# generator.net
KiCad netlist of a schematic drawn in EAGLE
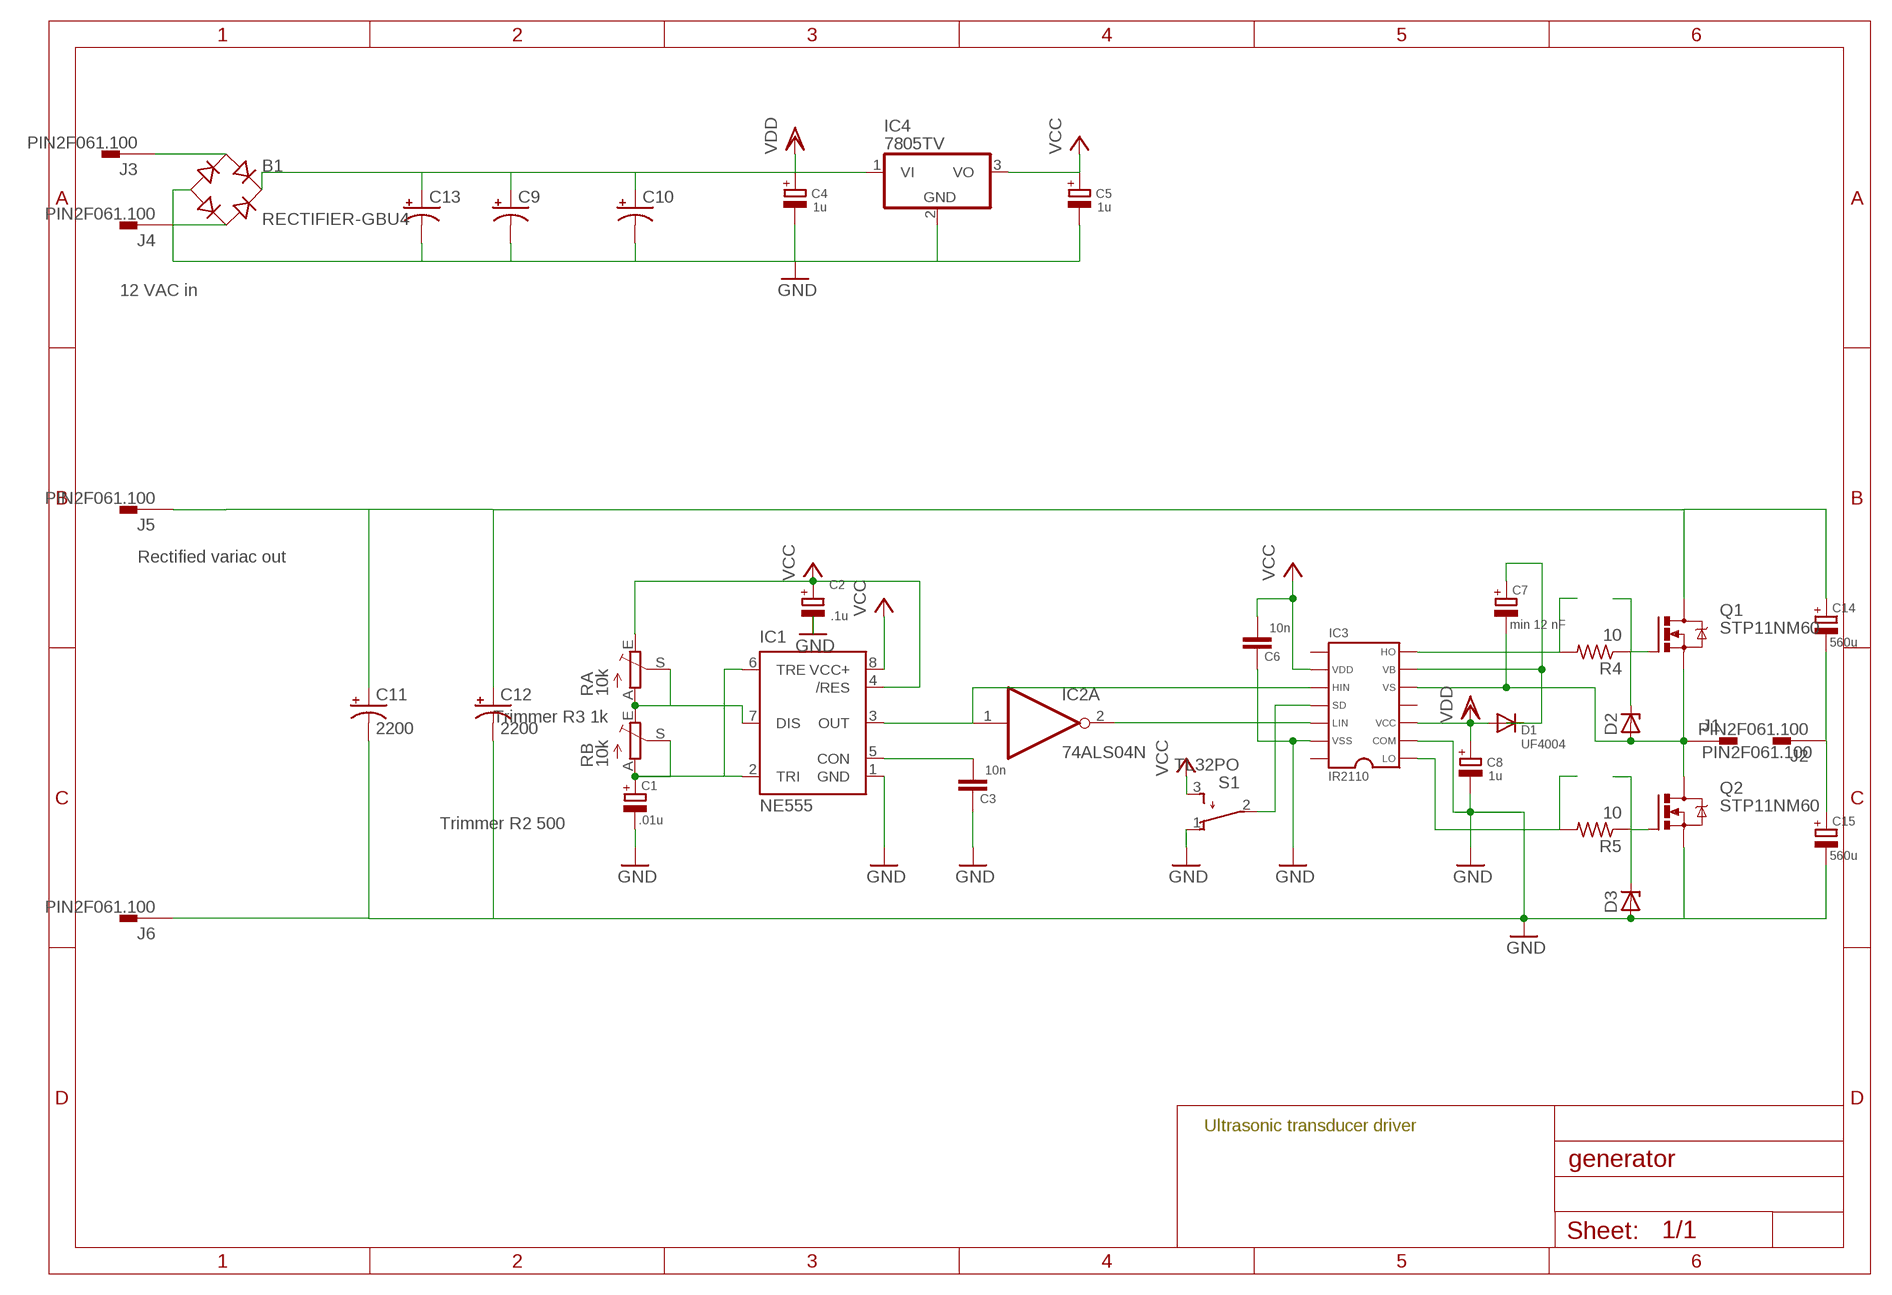
[diagram p0: schematic, sheet 1]

(export (version "E")
  (design (tool "Eeschema 10.0.6"))
  (components
    (comp (ref "B1")
      (value "RECTIFIER-GBU4")
      (footprint "eagle-import:GBU4")
      (libsource (lib "eagle-import") (part "RECTIFIER-GBU4"))
    )
    (comp (ref "C1")
      (value ".01u")
      (footprint "eagle-import:E5-8,5")
      (libsource (lib "eagle-import") (part "CPOL-EUE5-8.5"))
    )
    (comp (ref "C2")
      (value ".1u")
      (footprint "eagle-import:E5-8,5")
      (libsource (lib "eagle-import") (part "CPOL-EUE5-8.5"))
    )
    (comp (ref "C3")
      (value "10n")
      (footprint "eagle-import:C075-052X106")
      (libsource (lib "eagle-import") (part "C-EU075-052X106"))
    )
    (comp (ref "C4")
      (value "1u")
      (footprint "eagle-import:E5-8,5")
      (libsource (lib "eagle-import") (part "CPOL-EUE5-8.5"))
    )
    (comp (ref "C5")
      (value "1u")
      (footprint "eagle-import:E5-8,5")
      (libsource (lib "eagle-import") (part "CPOL-EUE5-8.5"))
    )
    (comp (ref "C6")
      (value "10n")
      (footprint "eagle-import:C075-052X106")
      (libsource (lib "eagle-import") (part "C-EU075-052X106"))
    )
    (comp (ref "C7")
      (value "min 12 nF")
      (footprint "eagle-import:E5-8,5")
      (libsource (lib "eagle-import") (part "CPOL-EUE5-8.5"))
    )
    (comp (ref "C8")
      (value "1u")
      (footprint "eagle-import:E5-8,5")
      (libsource (lib "eagle-import") (part "CPOL-EUE5-8.5"))
    )
    (comp (ref "C9")
      (value "CPOL-USE7.5-18")
      (footprint "eagle-import:E7,5-18")
      (libsource (lib "eagle-import") (part "CPOL-USE7.5-18"))
    )
    (comp (ref "C10")
      (value "CPOL-USE7.5-18")
      (footprint "eagle-import:E7,5-18")
      (libsource (lib "eagle-import") (part "CPOL-USE7.5-18"))
    )
    (comp (ref "C11")
      (value "2200")
      (footprint "eagle-import:EB35D")
      (libsource (lib "eagle-import") (part "CPOL-USE10-35"))
    )
    (comp (ref "C12")
      (value "2200")
      (footprint "eagle-import:EB35D")
      (libsource (lib "eagle-import") (part "CPOL-USE10-35"))
    )
    (comp (ref "C13")
      (value "CPOL-USE7.5-18")
      (footprint "eagle-import:E7,5-18")
      (libsource (lib "eagle-import") (part "CPOL-USE7.5-18"))
    )
    (comp (ref "C14")
      (value "560u")
      (footprint "eagle-import:E7,5-16")
      (libsource (lib "eagle-import") (part "CPOL-EUE7.5-16"))
    )
    (comp (ref "C15")
      (value "560u")
      (footprint "eagle-import:E7,5-16")
      (libsource (lib "eagle-import") (part "CPOL-EUE7.5-16"))
    )
    (comp (ref "D1")
      (value "UF4004")
      (footprint "eagle-import:D-7.5")
      (libsource (lib "eagle-import") (part "DIODE-D-7.5"))
    )
    (comp (ref "D2")
      (value "ZENER-DIODEZD-10")
      (footprint "eagle-import:ZDIO-10")
      (libsource (lib "eagle-import") (part "ZENER-DIODEZD-10"))
    )
    (comp (ref "D3")
      (value "ZENER-DIODEZD-10")
      (footprint "eagle-import:ZDIO-10")
      (libsource (lib "eagle-import") (part "ZENER-DIODEZD-10"))
    )
    (comp (ref "IC1")
      (value "NE555")
      (footprint "eagle-import:DIL-08")
      (fields (field (name "MF") "Arrow Electronics") (field (name "MPN") "NE555N"))
      (libsource (lib "eagle-import") (part "NE555"))
    )
    (comp (ref "IC2")
      (value "74ALS04N")
      (footprint "eagle-import:DIL14")
      (libsource (lib "eagle-import") (part "7404NALS"))
    )
    (comp (ref "IC3")
      (value "IR2110")
      (footprint "eagle-import:DIL14")
      (libsource (lib "eagle-import") (part "IR2110"))
    )
    (comp (ref "IC4")
      (value "7805TV")
      (footprint "eagle-import:TO220V")
      (libsource (lib "eagle-import") (part "78TV05"))
    )
    (comp (ref "J1")
      (value "PIN2F061.100")
      (footprint "eagle-import:F061.100")
      (libsource (lib "eagle-import") (part "PIN2F061.100"))
    )
    (comp (ref "J2")
      (value "PIN2F061.100")
      (footprint "eagle-import:F061.100")
      (libsource (lib "eagle-import") (part "PIN2F061.100"))
    )
    (comp (ref "J3")
      (value "PIN2F061.100")
      (footprint "eagle-import:F061.100")
      (libsource (lib "eagle-import") (part "PIN2F061.100"))
    )
    (comp (ref "J4")
      (value "PIN2F061.100")
      (footprint "eagle-import:F061.100")
      (libsource (lib "eagle-import") (part "PIN2F061.100"))
    )
    (comp (ref "J5")
      (value "PIN2F061.100")
      (footprint "eagle-import:F061.100")
      (libsource (lib "eagle-import") (part "PIN2F061.100"))
    )
    (comp (ref "J6")
      (value "PIN2F061.100")
      (footprint "eagle-import:F061.100")
      (libsource (lib "eagle-import") (part "PIN2F061.100"))
    )
    (comp (ref "Q1")
      (value "STP11NM60")
      (footprint "eagle-import:TO220BV")
      (libsource (lib "eagle-import") (part "IRF530"))
    )
    (comp (ref "Q2")
      (value "STP11NM60")
      (footprint "eagle-import:TO220BV")
      (libsource (lib "eagle-import") (part "IRF530"))
    )
    (comp (ref "R4")
      (value "10")
      (footprint "eagle-import:0207_10")
      (libsource (lib "eagle-import") (part "R-US_0207/10"))
    )
    (comp (ref "R5")
      (value "10")
      (footprint "eagle-import:0207_10")
      (libsource (lib "eagle-import") (part "R-US_0207/10"))
    )
    (comp (ref "RA")
      (value "10k")
      (footprint "eagle-import:LI10")
      (libsource (lib "eagle-import") (part "TRIM_EU-LI10"))
    )
    (comp (ref "RB")
      (value "10k")
      (footprint "eagle-import:LI10")
      (libsource (lib "eagle-import") (part "TRIM_EU-LI10"))
    )
    (comp (ref "S1")
      (value "TL32PO")
      (footprint "eagle-import:TL3XPO")
      (libsource (lib "eagle-import") (part "TL32PO"))
    )
  )
  (nets
    (net (code "1") (name "GND") (class "Default")
      (node (ref "B1") (pin "-") (pinfunction "-_-") (pintype "passive"))
      (node (ref "C1") (pin "-") (pinfunction "-_-") (pintype "passive"))
      (node (ref "C10") (pin "-") (pinfunction "-_-") (pintype "passive"))
      (node (ref "C11") (pin "-") (pinfunction "-_-") (pintype "passive"))
      (node (ref "C12") (pin "-") (pinfunction "-_-") (pintype "passive"))
      (node (ref "C13") (pin "-") (pinfunction "-_-") (pintype "passive"))
      (node (ref "C15") (pin "-") (pinfunction "-_-") (pintype "passive"))
      (node (ref "C2") (pin "-") (pinfunction "-_-") (pintype "passive"))
      (node (ref "C3") (pin "1") (pinfunction "1_1") (pintype "passive"))
      (node (ref "C4") (pin "-") (pinfunction "-_-") (pintype "passive"))
      (node (ref "C5") (pin "-") (pinfunction "-_-") (pintype "passive"))
      (node (ref "C6") (pin "1") (pinfunction "1_1") (pintype "passive"))
      (node (ref "C8") (pin "-") (pinfunction "-_-") (pintype "passive"))
      (node (ref "C9") (pin "-") (pinfunction "-_-") (pintype "passive"))
      (node (ref "D3") (pin "A") (pinfunction "A_A") (pintype "passive"))
      (node (ref "IC1") (pin "1") (pinfunction "GND_1") (pintype "power_in"))
      (node (ref "IC3") (pin "13") (pinfunction "13_13") (pintype "passive"))
      (node (ref "IC3") (pin "2") (pinfunction "2_2") (pintype "passive"))
      (node (ref "IC4") (pin "2") (pinfunction "GND_2") (pintype "passive"))
      (node (ref "J6") (pin "A1") (pinfunction "1_A1") (pintype "passive"))
      (node (ref "J6") (pin "A2") (pinfunction "1_A2") (pintype "passive"))
      (node (ref "Q2") (pin "S") (pinfunction "S_S") (pintype "passive"))
      (node (ref "S1") (pin "1") (pinfunction "O_1") (pintype "passive"))
    )
    (net (code "2") (name "Net-(B1-PadAC1)") (class "Default")
      (node (ref "B1") (pin "AC1") (pinfunction "AC1_AC1") (pintype "passive"))
      (node (ref "J3") (pin "A1") (pinfunction "1_A1") (pintype "passive"))
      (node (ref "J3") (pin "A2") (pinfunction "1_A2") (pintype "passive"))
    )
    (net (code "3") (name "Net-(B1-PadAC2)") (class "Default")
      (node (ref "B1") (pin "AC2") (pinfunction "AC2_AC2") (pintype "passive"))
      (node (ref "J4") (pin "A1") (pinfunction "1_A1") (pintype "passive"))
      (node (ref "J4") (pin "A2") (pinfunction "1_A2") (pintype "passive"))
    )
    (net (code "4") (name "Net-(C7-Pad+)") (class "Default")
      (node (ref "C7") (pin "+") (pinfunction "+_+") (pintype "passive"))
      (node (ref "D1") (pin "C") (pinfunction "C_C") (pintype "passive"))
      (node (ref "IC3") (pin "6") (pinfunction "6_6") (pintype "passive"))
    )
    (net (code "5") (name "Net-(C7-Pad-)") (class "Default")
      (node (ref "C7") (pin "-") (pinfunction "-_-") (pintype "passive"))
      (node (ref "D2") (pin "A") (pinfunction "A_A") (pintype "passive"))
      (node (ref "IC3") (pin "5") (pinfunction "5_5") (pintype "passive"))
      (node (ref "J1") (pin "A1") (pinfunction "1_A1") (pintype "passive"))
      (node (ref "J1") (pin "A2") (pinfunction "1_A2") (pintype "passive"))
      (node (ref "Q1") (pin "S") (pinfunction "S_S") (pintype "passive"))
      (node (ref "Q2") (pin "D") (pinfunction "D_D") (pintype "passive"))
    )
    (net (code "6") (name "Net-(C11-Pad+)") (class "Default")
      (node (ref "C11") (pin "+") (pinfunction "+_+") (pintype "passive"))
      (node (ref "C12") (pin "+") (pinfunction "+_+") (pintype "passive"))
      (node (ref "C14") (pin "+") (pinfunction "+_+") (pintype "passive"))
      (node (ref "J5") (pin "A1") (pinfunction "1_A1") (pintype "passive"))
      (node (ref "J5") (pin "A2") (pinfunction "1_A2") (pintype "passive"))
      (node (ref "Q1") (pin "D") (pinfunction "D_D") (pintype "passive"))
    )
    (net (code "7") (name "Net-(C14-Pad-)") (class "Default")
      (node (ref "C14") (pin "-") (pinfunction "-_-") (pintype "passive"))
      (node (ref "C15") (pin "+") (pinfunction "+_+") (pintype "passive"))
      (node (ref "J2") (pin "A1") (pinfunction "1_A1") (pintype "passive"))
      (node (ref "J2") (pin "A2") (pinfunction "1_A2") (pintype "passive"))
    )
    (net (code "8") (name "Net-(D2-PadC)") (class "Default")
      (node (ref "D2") (pin "C") (pinfunction "C_C") (pintype "passive"))
      (node (ref "Q1") (pin "G") (pinfunction "G_G") (pintype "passive"))
      (node (ref "R4") (pin "1") (pinfunction "1_1") (pintype "passive"))
    )
    (net (code "9") (name "Net-(D3-PadC)") (class "Default")
      (node (ref "D3") (pin "C") (pinfunction "C_C") (pintype "passive"))
      (node (ref "Q2") (pin "G") (pinfunction "G_G") (pintype "passive"))
      (node (ref "R5") (pin "1") (pinfunction "1_1") (pintype "passive"))
    )
    (net (code "10") (name "Net-(IC1-CON)") (class "Default")
      (node (ref "C3") (pin "2") (pinfunction "2_2") (pintype "passive"))
      (node (ref "IC1") (pin "5") (pinfunction "CON_5") (pintype "input"))
    )
    (net (code "11") (name "Net-(IC1-DIS)") (class "Default")
      (node (ref "IC1") (pin "7") (pinfunction "DIS_7") (pintype "input"))
      (node (ref "RA") (pin "A") (pinfunction "A_A") (pintype "passive"))
      (node (ref "RA") (pin "S") (pinfunction "S_S") (pintype "passive"))
      (node (ref "RB") (pin "E") (pinfunction "E_E") (pintype "passive"))
    )
    (net (code "12") (name "Net-(IC1-OUT)") (class "Default")
      (node (ref "IC1") (pin "3") (pinfunction "OUT_3") (pintype "output"))
      (node (ref "IC2") (pin "1") (pinfunction "I_1") (pintype "input"))
      (node (ref "IC3") (pin "10") (pinfunction "10_10") (pintype "passive"))
    )
    (net (code "13") (name "Net-(IC1-TRE)") (class "Default")
      (node (ref "C1") (pin "+") (pinfunction "+_+") (pintype "passive"))
      (node (ref "IC1") (pin "2") (pinfunction "TRI_2") (pintype "input"))
      (node (ref "IC1") (pin "6") (pinfunction "TRE_6") (pintype "input"))
      (node (ref "RB") (pin "A") (pinfunction "A_A") (pintype "passive"))
      (node (ref "RB") (pin "S") (pinfunction "S_S") (pintype "passive"))
    )
    (net (code "14") (name "Net-(IC2A-O)") (class "Default")
      (node (ref "IC2") (pin "2") (pinfunction "O_2") (pintype "output"))
      (node (ref "IC3") (pin "12") (pinfunction "12_12") (pintype "passive"))
    )
    (net (code "15") (name "Net-(IC3-Pad1)") (class "Default")
      (node (ref "IC3") (pin "1") (pinfunction "1_1") (pintype "passive"))
      (node (ref "R5") (pin "2") (pinfunction "2_2") (pintype "passive"))
    )
    (net (code "16") (name "Net-(IC3-Pad7)") (class "Default")
      (node (ref "IC3") (pin "7") (pinfunction "7_7") (pintype "passive"))
      (node (ref "R4") (pin "2") (pinfunction "2_2") (pintype "passive"))
    )
    (net (code "17") (name "Net-(S1-P)") (class "Default")
      (node (ref "IC3") (pin "11") (pinfunction "11_11") (pintype "passive"))
      (node (ref "S1") (pin "2") (pinfunction "P_2") (pintype "passive"))
    )
    (net (code "18") (name "VCC") (class "Default")
      (node (ref "C2") (pin "+") (pinfunction "+_+") (pintype "passive"))
      (node (ref "C5") (pin "+") (pinfunction "+_+") (pintype "passive"))
      (node (ref "C6") (pin "2") (pinfunction "2_2") (pintype "passive"))
      (node (ref "IC1") (pin "4") (pinfunction "/RES_4") (pintype "input"))
      (node (ref "IC1") (pin "8") (pinfunction "VCC+_8") (pintype "power_in"))
      (node (ref "IC3") (pin "9") (pinfunction "9_9") (pintype "passive"))
      (node (ref "IC4") (pin "3") (pinfunction "VO_3") (pintype "passive"))
      (node (ref "RA") (pin "E") (pinfunction "E_E") (pintype "passive"))
      (node (ref "S1") (pin "3") (pinfunction "S_3") (pintype "passive"))
    )
    (net (code "19") (name "VDD") (class "Default")
      (node (ref "B1") (pin "+") (pinfunction "+_+") (pintype "passive"))
      (node (ref "C10") (pin "+") (pinfunction "+_+") (pintype "passive"))
      (node (ref "C13") (pin "+") (pinfunction "+_+") (pintype "passive"))
      (node (ref "C4") (pin "+") (pinfunction "+_+") (pintype "passive"))
      (node (ref "C8") (pin "+") (pinfunction "+_+") (pintype "passive"))
      (node (ref "C9") (pin "+") (pinfunction "+_+") (pintype "passive"))
      (node (ref "D1") (pin "A") (pinfunction "A_A") (pintype "passive"))
      (node (ref "IC3") (pin "3") (pinfunction "3_3") (pintype "passive"))
      (node (ref "IC4") (pin "1") (pinfunction "VI_1") (pintype "input"))
    )
    (net (code "20") (name "unconnected-(IC3-Pad4)") (class "Default")
      (node (ref "IC3") (pin "4") (pinfunction "4_4") (pintype "passive"))
    )
    (net (code "21") (name "unconnected-(IC3-Pad8)") (class "Default")
      (node (ref "IC3") (pin "8") (pinfunction "8_8") (pintype "passive"))
    )
    (net (code "22") (name "unconnected-(IC3-Pad14)") (class "Default")
      (node (ref "IC3") (pin "14") (pinfunction "14_14") (pintype "passive"))
    )
  )
)
